# LED_PCB.net
KiCad netlist of a schematic drawn in EAGLE
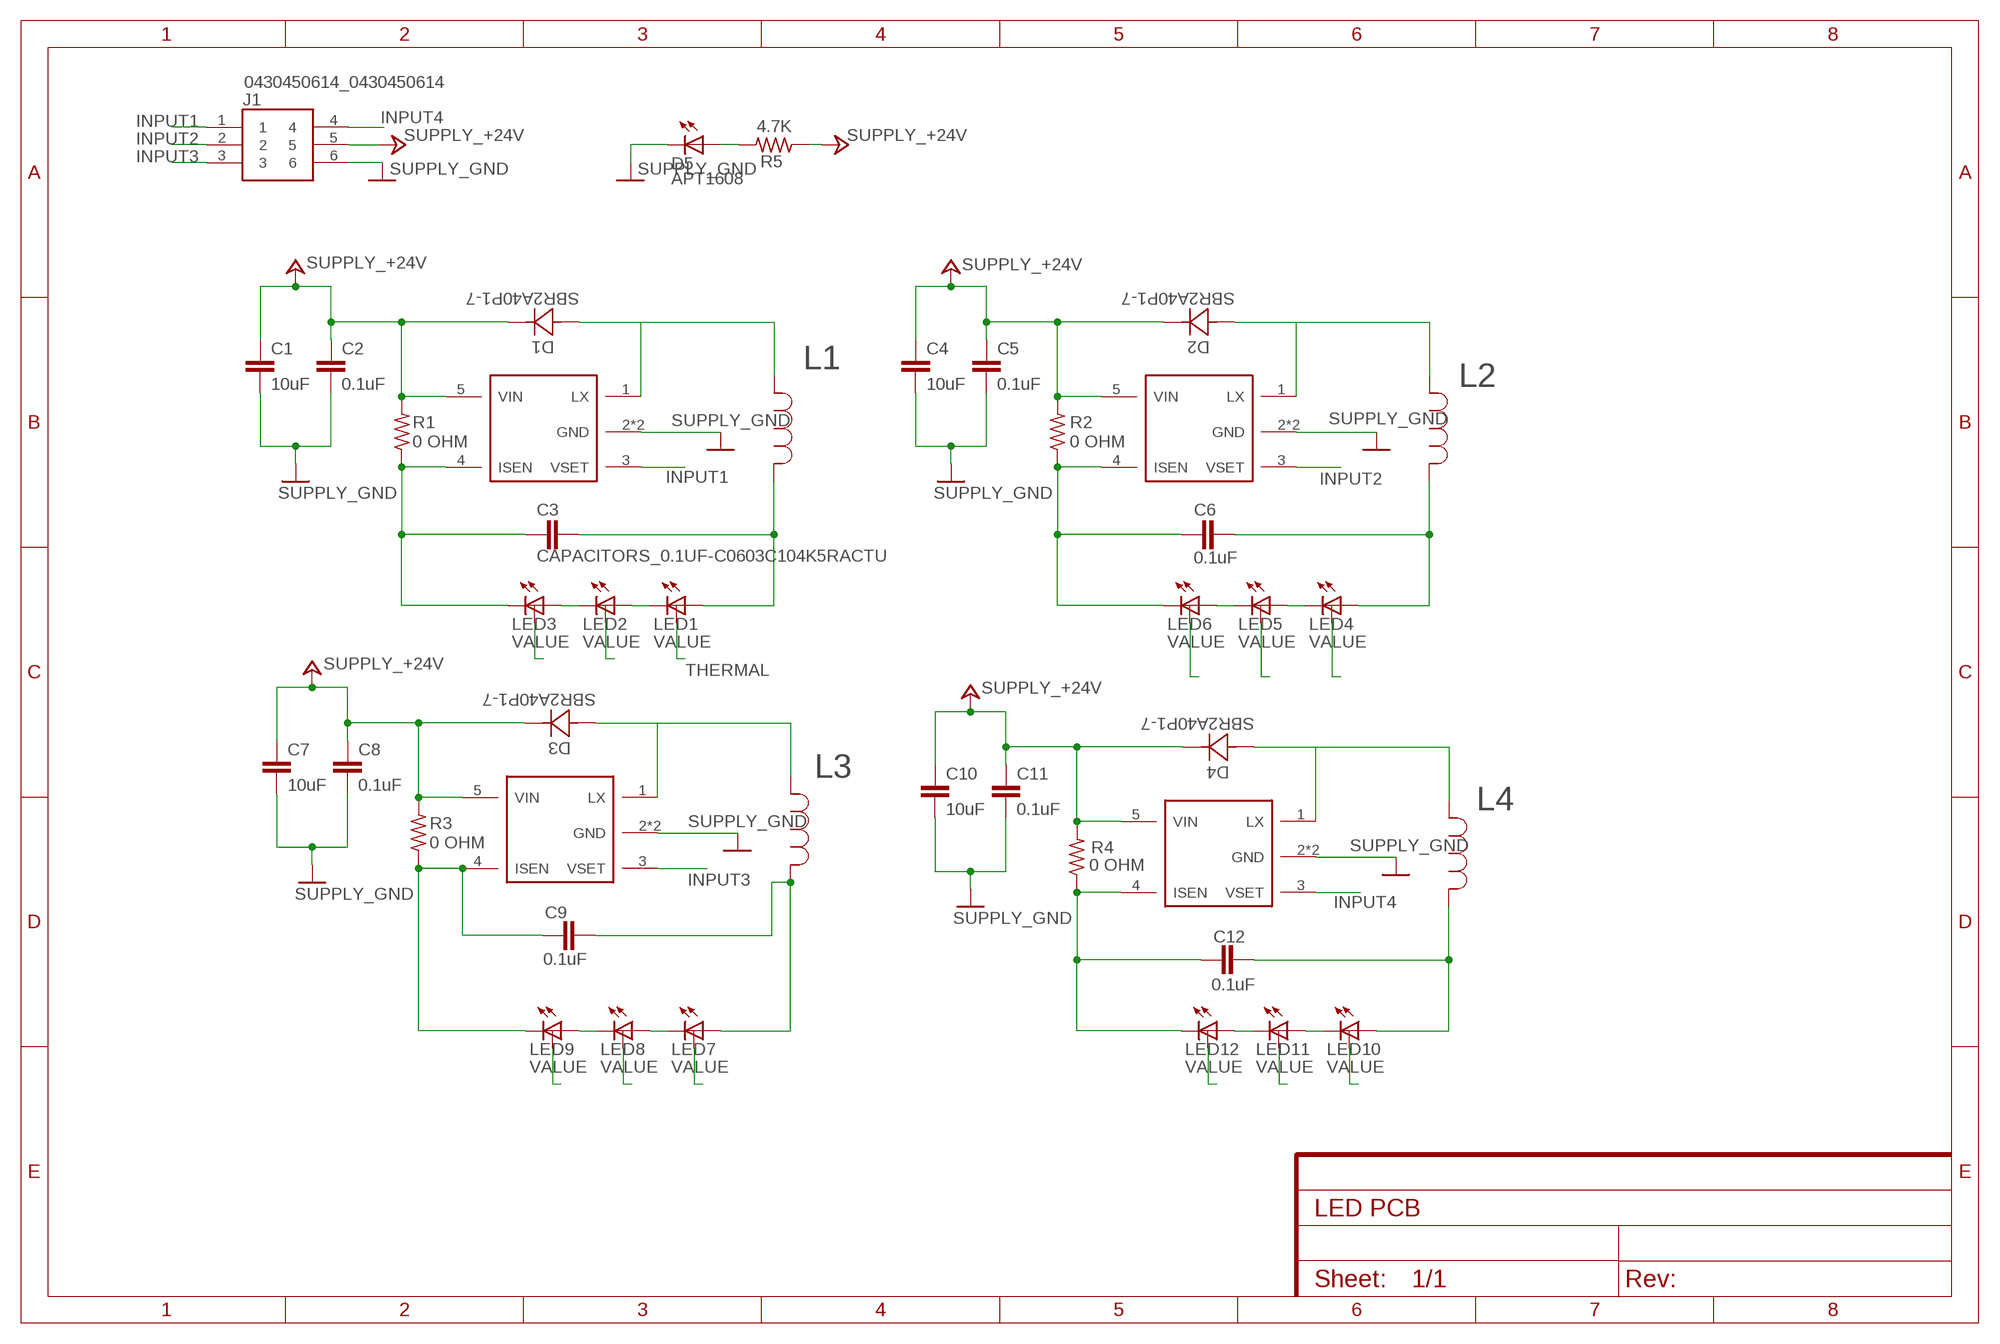
[diagram p0: schematic, sheet 1]

(export (version "E")
  (design (tool "Eeschema 10.0.6"))
  (components
    (comp (ref "C1")
      (value "10uF")
      (footprint "eagle-import:CAPACITORS_C0805")
      (fields (field (name "MANUFACTURER") "Taiyo Yuden") (field (name "MPN") "GMK212BBJ106KG-T"))
      (libsource (lib "eagle-import") (part "CAPACITORS_10UF-GMK212BBJ106KG-T"))
    )
    (comp (ref "C2")
      (value "0.1uF")
      (footprint "eagle-import:CAPACITORS_C0603")
      (fields (field (name "MANUFACTURER") "Kemet") (field (name "MPN") "C0603C104K5RACTU"))
      (libsource (lib "eagle-import") (part "CAPACITORS_0.1UF-C0603C104K5RACTU"))
    )
    (comp (ref "C3")
      (value "CAPACITORS_0.1UF-C0603C104K5RACTU")
      (footprint "eagle-import:CAPACITORS_C0603")
      (fields (field (name "MANUFACTURER") "Kemet") (field (name "MPN") "C0603C104K5RACTU"))
      (libsource (lib "eagle-import") (part "CAPACITORS_0.1UF-C0603C104K5RACTU"))
    )
    (comp (ref "C4")
      (value "10uF")
      (footprint "eagle-import:CAPACITORS_C0805")
      (fields (field (name "MANUFACTURER") "Taiyo Yuden") (field (name "MPN") "GMK212BBJ106KG-T"))
      (libsource (lib "eagle-import") (part "CAPACITORS_10UF-GMK212BBJ106KG-T"))
    )
    (comp (ref "C5")
      (value "0.1uF")
      (footprint "eagle-import:CAPACITORS_C0603")
      (fields (field (name "MANUFACTURER") "Kemet") (field (name "MPN") "C0603C104K5RACTU"))
      (libsource (lib "eagle-import") (part "CAPACITORS_0.1UF-C0603C104K5RACTU"))
    )
    (comp (ref "C6")
      (value "0.1uF")
      (footprint "eagle-import:CAPACITORS_C0603")
      (fields (field (name "MANUFACTURER") "Kemet") (field (name "MPN") "C0603C104K5RACTU"))
      (libsource (lib "eagle-import") (part "CAPACITORS_0.1UF-C0603C104K5RACTU"))
    )
    (comp (ref "C7")
      (value "10uF")
      (footprint "eagle-import:CAPACITORS_C0805")
      (fields (field (name "MANUFACTURER") "Taiyo Yuden") (field (name "MPN") "GMK212BBJ106KG-T"))
      (libsource (lib "eagle-import") (part "CAPACITORS_10UF-GMK212BBJ106KG-T"))
    )
    (comp (ref "C8")
      (value "0.1uF")
      (footprint "eagle-import:CAPACITORS_C0603")
      (fields (field (name "MANUFACTURER") "Kemet") (field (name "MPN") "C0603C104K5RACTU"))
      (libsource (lib "eagle-import") (part "CAPACITORS_0.1UF-C0603C104K5RACTU"))
    )
    (comp (ref "C9")
      (value "0.1uF")
      (footprint "eagle-import:CAPACITORS_C0603")
      (fields (field (name "MANUFACTURER") "Kemet") (field (name "MPN") "C0603C104K5RACTU"))
      (libsource (lib "eagle-import") (part "CAPACITORS_0.1UF-C0603C104K5RACTU"))
    )
    (comp (ref "C10")
      (value "10uF")
      (footprint "eagle-import:CAPACITORS_C0805")
      (fields (field (name "MANUFACTURER") "Taiyo Yuden") (field (name "MPN") "GMK212BBJ106KG-T"))
      (libsource (lib "eagle-import") (part "CAPACITORS_10UF-GMK212BBJ106KG-T"))
    )
    (comp (ref "C11")
      (value "0.1uF")
      (footprint "eagle-import:CAPACITORS_C0603")
      (fields (field (name "MANUFACTURER") "Kemet") (field (name "MPN") "C0603C104K5RACTU"))
      (libsource (lib "eagle-import") (part "CAPACITORS_0.1UF-C0603C104K5RACTU"))
    )
    (comp (ref "C12")
      (value "0.1uF")
      (footprint "eagle-import:CAPACITORS_C0603")
      (fields (field (name "MANUFACTURER") "Kemet") (field (name "MPN") "C0603C104K5RACTU"))
      (libsource (lib "eagle-import") (part "CAPACITORS_0.1UF-C0603C104K5RACTU"))
    )
    (comp (ref "D1")
      (value "SBR2A40P1-7")
      (footprint "eagle-import:DIODES_POWERDI123")
      (fields (field (name "MANUFACTURER") "Diodes Incorporated"))
      (libsource (lib "eagle-import") (part "DIODES_SBR2A40P1-7"))
    )
    (comp (ref "D2")
      (value "SBR2A40P1-7")
      (footprint "eagle-import:DIODES_POWERDI123")
      (fields (field (name "MANUFACTURER") "Diodes Incorporated"))
      (libsource (lib "eagle-import") (part "DIODES_SBR2A40P1-7"))
    )
    (comp (ref "D3")
      (value "SBR2A40P1-7")
      (footprint "eagle-import:DIODES_POWERDI123")
      (fields (field (name "MANUFACTURER") "Diodes Incorporated"))
      (libsource (lib "eagle-import") (part "DIODES_SBR2A40P1-7"))
    )
    (comp (ref "D4")
      (value "SBR2A40P1-7")
      (footprint "eagle-import:DIODES_POWERDI123")
      (fields (field (name "MANUFACTURER") "Diodes Incorporated"))
      (libsource (lib "eagle-import") (part "DIODES_SBR2A40P1-7"))
    )
    (comp (ref "D5")
      (value "APT1608")
      (footprint "eagle-import:DIODES_CHIPLED_0603")
      (fields (field (name "MANUFACTURER") "Kingbright") (field (name "MPN") "APT1608CGCK"))
      (libsource (lib "eagle-import") (part "DIODES_APT1608CGCK"))
    )
    (comp (ref "J1")
      (value "0430450614_0430450614")
      (footprint "eagle-import:0430450614_MOLEX_0430450614")
      (fields (field (name "MF") "Molex") (field (name "MP") "0430450614"))
      (libsource (lib "eagle-import") (part "0430450614_0430450614"))
    )
    (comp (ref "L1")
      (value "INDUCTORS_100UH_BOURNES")
      (footprint "eagle-import:INDUCTORS_IND_BOURNS_SDR1307")
      (libsource (lib "eagle-import") (part "INDUCTORS_100UH_BOURNES"))
    )
    (comp (ref "L2")
      (value "INDUCTORS_100UH_BOURNES")
      (footprint "eagle-import:INDUCTORS_IND_BOURNS_SDR1307")
      (libsource (lib "eagle-import") (part "INDUCTORS_100UH_BOURNES"))
    )
    (comp (ref "L3")
      (value "INDUCTORS_100UH_BOURNES")
      (footprint "eagle-import:INDUCTORS_IND_BOURNS_SDR1307")
      (libsource (lib "eagle-import") (part "INDUCTORS_100UH_BOURNES"))
    )
    (comp (ref "L4")
      (value "INDUCTORS_100UH_BOURNES")
      (footprint "eagle-import:INDUCTORS_IND_BOURNS_SDR1307")
      (libsource (lib "eagle-import") (part "INDUCTORS_100UH_BOURNES"))
    )
    (comp (ref "LED1")
      (value "PFCEDU_V4_TOMASZEWSKI_LED_W/THERM-CREE_XP-E2")
      (footprint "eagle-import:TOMASZEWSKI_CREE-XLAMP@1")
      (libsource (lib "eagle-import") (part "PFCEDU_V4_TOMASZEWSKI_LED_W/THERM-CREE_XP-E2"))
    )
    (comp (ref "LED2")
      (value "TOMASZEWSKI_LED_W/THERM-CREE_XP-E2")
      (footprint "eagle-import:TOMASZEWSKI_CREE-XLAMP@1")
      (fields (field (name "SPICEPREFIX") "J"))
      (libsource (lib "eagle-import") (part "PFCEDU_V4_TOMASZEWSKI_LED_W/THERM-CREE_XP-E2"))
    )
    (comp (ref "LED3")
      (value "PFCEDU_V4_TOMASZEWSKI_LED_W/THERM-CREE_XP-E2")
      (footprint "eagle-import:TOMASZEWSKI_CREE-XLAMP@1")
      (libsource (lib "eagle-import") (part "PFCEDU_V4_TOMASZEWSKI_LED_W/THERM-CREE_XP-E2"))
    )
    (comp (ref "LED4")
      (value "PFCEDU_V4_TOMASZEWSKI_LED_W/THERM-CREE_XP-E2")
      (footprint "eagle-import:TOMASZEWSKI_CREE-XLAMP@1")
      (libsource (lib "eagle-import") (part "PFCEDU_V4_TOMASZEWSKI_LED_W/THERM-CREE_XP-E2"))
    )
    (comp (ref "LED5")
      (value "PFCEDU_V4_TOMASZEWSKI_LED_W/THERM-CREE_XP-E2")
      (footprint "eagle-import:TOMASZEWSKI_CREE-XLAMP@1")
      (libsource (lib "eagle-import") (part "PFCEDU_V4_TOMASZEWSKI_LED_W/THERM-CREE_XP-E2"))
    )
    (comp (ref "LED6")
      (value "PFCEDU_V4_TOMASZEWSKI_LED_W/THERM-CREE_XP-E2")
      (footprint "eagle-import:TOMASZEWSKI_CREE-XLAMP@1")
      (libsource (lib "eagle-import") (part "PFCEDU_V4_TOMASZEWSKI_LED_W/THERM-CREE_XP-E2"))
    )
    (comp (ref "LED7")
      (value "PFCEDU_V4_TOMASZEWSKI_LED_W/THERM-CREE_XP-E2")
      (footprint "eagle-import:TOMASZEWSKI_CREE-XLAMP@1")
      (libsource (lib "eagle-import") (part "PFCEDU_V4_TOMASZEWSKI_LED_W/THERM-CREE_XP-E2"))
    )
    (comp (ref "LED8")
      (value "PFCEDU_V4_TOMASZEWSKI_LED_W/THERM-CREE_XP-E2")
      (footprint "eagle-import:TOMASZEWSKI_CREE-XLAMP@1")
      (libsource (lib "eagle-import") (part "PFCEDU_V4_TOMASZEWSKI_LED_W/THERM-CREE_XP-E2"))
    )
    (comp (ref "LED9")
      (value "PFCEDU_V4_TOMASZEWSKI_LED_W/THERM-CREE_XP-E2")
      (footprint "eagle-import:TOMASZEWSKI_CREE-XLAMP@1")
      (libsource (lib "eagle-import") (part "PFCEDU_V4_TOMASZEWSKI_LED_W/THERM-CREE_XP-E2"))
    )
    (comp (ref "LED10")
      (value "PFCEDU_V4_TOMASZEWSKI_LED_W/THERM-CREE_XP-E2")
      (footprint "eagle-import:TOMASZEWSKI_CREE-XLAMP@1")
      (libsource (lib "eagle-import") (part "PFCEDU_V4_TOMASZEWSKI_LED_W/THERM-CREE_XP-E2"))
    )
    (comp (ref "LED11")
      (value "PFCEDU_V4_TOMASZEWSKI_LED_W/THERM-CREE_XP-E2")
      (footprint "eagle-import:TOMASZEWSKI_CREE-XLAMP@1")
      (libsource (lib "eagle-import") (part "PFCEDU_V4_TOMASZEWSKI_LED_W/THERM-CREE_XP-E2"))
    )
    (comp (ref "LED12")
      (value "PFCEDU_V4_TOMASZEWSKI_LED_W/THERM-CREE_XP-E2")
      (footprint "eagle-import:TOMASZEWSKI_CREE-XLAMP@1")
      (libsource (lib "eagle-import") (part "PFCEDU_V4_TOMASZEWSKI_LED_W/THERM-CREE_XP-E2"))
    )
    (comp (ref "R1")
      (value "0 OHM")
      (footprint "eagle-import:RESISTORS_RC0603N")
      (fields (field (name "MANUFACTURER") "Yageo") (field (name "MPN") "RC0603JR-070RL"))
      (libsource (lib "eagle-import") (part "RESISTORS_0OHM-RC0603JR-070RL"))
    )
    (comp (ref "R2")
      (value "0 OHM")
      (footprint "eagle-import:RESISTORS_RC0603N")
      (fields (field (name "MANUFACTURER") "Yageo") (field (name "MPN") "RC0603JR-070RL"))
      (libsource (lib "eagle-import") (part "RESISTORS_0OHM-RC0603JR-070RL"))
    )
    (comp (ref "R3")
      (value "0 OHM")
      (footprint "eagle-import:RESISTORS_RC0603N")
      (fields (field (name "MANUFACTURER") "Yageo") (field (name "MPN") "RC0603JR-070RL"))
      (libsource (lib "eagle-import") (part "RESISTORS_0OHM-RC0603JR-070RL"))
    )
    (comp (ref "R4")
      (value "0 OHM")
      (footprint "eagle-import:RESISTORS_RC0603N")
      (fields (field (name "MANUFACTURER") "Yageo") (field (name "MPN") "RC0603JR-070RL"))
      (libsource (lib "eagle-import") (part "RESISTORS_0OHM-RC0603JR-070RL"))
    )
    (comp (ref "R5")
      (value "4.7K")
      (footprint "eagle-import:RESISTORS_R1206")
      (fields (field (name "MANUFACTURER") "Yageo") (field (name "MPN") "RC1206JR-074K7L"))
      (libsource (lib "eagle-import") (part "RESISTORS_4.7K-RC1206JR-074K7L"))
    )
    (comp (ref "U$1")
      (value "DRIVER-IC_AL8861")
      (footprint "eagle-import:DRIVER-IC_AL8861")
      (libsource (lib "eagle-import") (part "DRIVER-IC_AL8861"))
    )
    (comp (ref "U$3")
      (value "DRIVER-IC_AL8861")
      (footprint "eagle-import:DRIVER-IC_AL8861")
      (libsource (lib "eagle-import") (part "DRIVER-IC_AL8861"))
    )
    (comp (ref "U$5")
      (value "DRIVER-IC_AL8861")
      (footprint "eagle-import:DRIVER-IC_AL8861")
      (libsource (lib "eagle-import") (part "DRIVER-IC_AL8861"))
    )
    (comp (ref "U$7")
      (value "DRIVER-IC_AL8861")
      (footprint "eagle-import:DRIVER-IC_AL8861")
      (libsource (lib "eagle-import") (part "DRIVER-IC_AL8861"))
    )
  )
  (nets
    (net (code "1") (name "/INPUT1") (class "Default")
      (node (ref "J1") (pin "1") (pinfunction "1_1") (pintype "passive"))
      (node (ref "U$1") (pin "3") (pinfunction "VSET_3") (pintype "bidirectional"))
    )
    (net (code "2") (name "/INPUT2") (class "Default")
      (node (ref "J1") (pin "2") (pinfunction "2_2") (pintype "passive"))
      (node (ref "U$3") (pin "3") (pinfunction "VSET_3") (pintype "bidirectional"))
    )
    (net (code "3") (name "/INPUT3") (class "Default")
      (node (ref "J1") (pin "3") (pinfunction "3_3") (pintype "passive"))
      (node (ref "U$5") (pin "3") (pinfunction "VSET_3") (pintype "bidirectional"))
    )
    (net (code "4") (name "/INPUT4") (class "Default")
      (node (ref "J1") (pin "4") (pinfunction "4_4") (pintype "passive"))
      (node (ref "U$7") (pin "3") (pinfunction "VSET_3") (pintype "bidirectional"))
    )
    (net (code "5") (name "/THERMAL") (class "Default")
      (node (ref "LED1") (pin "THERM") (pinfunction "THERM_THERM") (pintype "bidirectional"))
    )
    (net (code "6") (name "Net-(C3-Pad2)") (class "Default")
      (node (ref "C3") (pin "2") (pinfunction "2_2") (pintype "passive"))
      (node (ref "L1") (pin "1") (pinfunction "1_1") (pintype "passive"))
      (node (ref "LED1") (pin "A") (pinfunction "A_A") (pintype "passive"))
      (node (ref "LED1") (pin "A@1") (pinfunction "A_A@1") (pintype "passive"))
    )
    (net (code "7") (name "Net-(C6-Pad2)") (class "Default")
      (node (ref "C6") (pin "2") (pinfunction "2_2") (pintype "passive"))
      (node (ref "L2") (pin "1") (pinfunction "1_1") (pintype "passive"))
      (node (ref "LED4") (pin "A") (pinfunction "A_A") (pintype "passive"))
      (node (ref "LED4") (pin "A@1") (pinfunction "A_A@1") (pintype "passive"))
    )
    (net (code "8") (name "Net-(C9-Pad2)") (class "Default")
      (node (ref "C9") (pin "2") (pinfunction "2_2") (pintype "passive"))
      (node (ref "L3") (pin "1") (pinfunction "1_1") (pintype "passive"))
      (node (ref "LED7") (pin "A") (pinfunction "A_A") (pintype "passive"))
      (node (ref "LED7") (pin "A@1") (pinfunction "A_A@1") (pintype "passive"))
    )
    (net (code "9") (name "Net-(C12-Pad2)") (class "Default")
      (node (ref "C12") (pin "2") (pinfunction "2_2") (pintype "passive"))
      (node (ref "L4") (pin "1") (pinfunction "1_1") (pintype "passive"))
      (node (ref "LED10") (pin "A") (pinfunction "A_A") (pintype "passive"))
      (node (ref "LED10") (pin "A@1") (pinfunction "A_A@1") (pintype "passive"))
    )
    (net (code "10") (name "Net-(D5-PadA)") (class "Default")
      (node (ref "D5") (pin "A") (pinfunction "A_A") (pintype "passive"))
      (node (ref "R5") (pin "2") (pinfunction "2_2") (pintype "passive"))
    )
    (net (code "11") (name "Net-(LED1-C-PadC@1)") (class "Default")
      (node (ref "LED1") (pin "C") (pinfunction "C_C") (pintype "passive"))
      (node (ref "LED1") (pin "C@1") (pinfunction "C_C@1") (pintype "passive"))
      (node (ref "LED2") (pin "A") (pinfunction "A_A") (pintype "passive"))
      (node (ref "LED2") (pin "A@1") (pinfunction "A_A@1") (pintype "passive"))
    )
    (net (code "12") (name "Net-(LED2-C-PadC@1)") (class "Default")
      (node (ref "LED2") (pin "C") (pinfunction "C_C") (pintype "passive"))
      (node (ref "LED2") (pin "C@1") (pinfunction "C_C@1") (pintype "passive"))
      (node (ref "LED3") (pin "A") (pinfunction "A_A") (pintype "passive"))
      (node (ref "LED3") (pin "A@1") (pinfunction "A_A@1") (pintype "passive"))
    )
    (net (code "13") (name "Net-(LED4-C-PadC@1)") (class "Default")
      (node (ref "LED4") (pin "C") (pinfunction "C_C") (pintype "passive"))
      (node (ref "LED4") (pin "C@1") (pinfunction "C_C@1") (pintype "passive"))
      (node (ref "LED5") (pin "A") (pinfunction "A_A") (pintype "passive"))
      (node (ref "LED5") (pin "A@1") (pinfunction "A_A@1") (pintype "passive"))
    )
    (net (code "14") (name "Net-(LED5-C-PadC@1)") (class "Default")
      (node (ref "LED5") (pin "C") (pinfunction "C_C") (pintype "passive"))
      (node (ref "LED5") (pin "C@1") (pinfunction "C_C@1") (pintype "passive"))
      (node (ref "LED6") (pin "A") (pinfunction "A_A") (pintype "passive"))
      (node (ref "LED6") (pin "A@1") (pinfunction "A_A@1") (pintype "passive"))
    )
    (net (code "15") (name "Net-(LED7-C-PadC@1)") (class "Default")
      (node (ref "LED7") (pin "C") (pinfunction "C_C") (pintype "passive"))
      (node (ref "LED7") (pin "C@1") (pinfunction "C_C@1") (pintype "passive"))
      (node (ref "LED8") (pin "A") (pinfunction "A_A") (pintype "passive"))
      (node (ref "LED8") (pin "A@1") (pinfunction "A_A@1") (pintype "passive"))
    )
    (net (code "16") (name "Net-(LED8-C-PadC@1)") (class "Default")
      (node (ref "LED8") (pin "C") (pinfunction "C_C") (pintype "passive"))
      (node (ref "LED8") (pin "C@1") (pinfunction "C_C@1") (pintype "passive"))
      (node (ref "LED9") (pin "A") (pinfunction "A_A") (pintype "passive"))
      (node (ref "LED9") (pin "A@1") (pinfunction "A_A@1") (pintype "passive"))
    )
    (net (code "17") (name "Net-(LED10-C-PadC@1)") (class "Default")
      (node (ref "LED10") (pin "C") (pinfunction "C_C") (pintype "passive"))
      (node (ref "LED10") (pin "C@1") (pinfunction "C_C@1") (pintype "passive"))
      (node (ref "LED11") (pin "A") (pinfunction "A_A") (pintype "passive"))
      (node (ref "LED11") (pin "A@1") (pinfunction "A_A@1") (pintype "passive"))
    )
    (net (code "18") (name "Net-(LED11-C-PadC@1)") (class "Default")
      (node (ref "LED11") (pin "C") (pinfunction "C_C") (pintype "passive"))
      (node (ref "LED11") (pin "C@1") (pinfunction "C_C@1") (pintype "passive"))
      (node (ref "LED12") (pin "A") (pinfunction "A_A") (pintype "passive"))
      (node (ref "LED12") (pin "A@1") (pinfunction "A_A@1") (pintype "passive"))
    )
    (net (code "19") (name "Net-(U$1-ISEN)") (class "Default")
      (node (ref "C3") (pin "1") (pinfunction "1_1") (pintype "passive"))
      (node (ref "LED3") (pin "C") (pinfunction "C_C") (pintype "passive"))
      (node (ref "LED3") (pin "C@1") (pinfunction "C_C@1") (pintype "passive"))
      (node (ref "R1") (pin "1") (pinfunction "1_1") (pintype "passive"))
      (node (ref "U$1") (pin "4") (pinfunction "ISEN_4") (pintype "bidirectional"))
    )
    (net (code "20") (name "Net-(U$1-LX)") (class "Default")
      (node (ref "D1") (pin "+") (pinfunction "+_+") (pintype "passive"))
      (node (ref "L1") (pin "2") (pinfunction "2_2") (pintype "passive"))
      (node (ref "U$1") (pin "1") (pinfunction "LX_1") (pintype "bidirectional"))
    )
    (net (code "21") (name "Net-(U$3-ISEN)") (class "Default")
      (node (ref "C6") (pin "1") (pinfunction "1_1") (pintype "passive"))
      (node (ref "LED6") (pin "C") (pinfunction "C_C") (pintype "passive"))
      (node (ref "LED6") (pin "C@1") (pinfunction "C_C@1") (pintype "passive"))
      (node (ref "R2") (pin "1") (pinfunction "1_1") (pintype "passive"))
      (node (ref "U$3") (pin "4") (pinfunction "ISEN_4") (pintype "bidirectional"))
    )
    (net (code "22") (name "Net-(U$3-LX)") (class "Default")
      (node (ref "D2") (pin "+") (pinfunction "+_+") (pintype "passive"))
      (node (ref "L2") (pin "2") (pinfunction "2_2") (pintype "passive"))
      (node (ref "U$3") (pin "1") (pinfunction "LX_1") (pintype "bidirectional"))
    )
    (net (code "23") (name "Net-(U$5-ISEN)") (class "Default")
      (node (ref "C9") (pin "1") (pinfunction "1_1") (pintype "passive"))
      (node (ref "LED9") (pin "C") (pinfunction "C_C") (pintype "passive"))
      (node (ref "LED9") (pin "C@1") (pinfunction "C_C@1") (pintype "passive"))
      (node (ref "R3") (pin "1") (pinfunction "1_1") (pintype "passive"))
      (node (ref "U$5") (pin "4") (pinfunction "ISEN_4") (pintype "bidirectional"))
    )
    (net (code "24") (name "Net-(U$5-LX)") (class "Default")
      (node (ref "D3") (pin "+") (pinfunction "+_+") (pintype "passive"))
      (node (ref "L3") (pin "2") (pinfunction "2_2") (pintype "passive"))
      (node (ref "U$5") (pin "1") (pinfunction "LX_1") (pintype "bidirectional"))
    )
    (net (code "25") (name "Net-(U$7-ISEN)") (class "Default")
      (node (ref "C12") (pin "1") (pinfunction "1_1") (pintype "passive"))
      (node (ref "LED12") (pin "C") (pinfunction "C_C") (pintype "passive"))
      (node (ref "LED12") (pin "C@1") (pinfunction "C_C@1") (pintype "passive"))
      (node (ref "R4") (pin "1") (pinfunction "1_1") (pintype "passive"))
      (node (ref "U$7") (pin "4") (pinfunction "ISEN_4") (pintype "bidirectional"))
    )
    (net (code "26") (name "Net-(U$7-LX)") (class "Default")
      (node (ref "D4") (pin "+") (pinfunction "+_+") (pintype "passive"))
      (node (ref "L4") (pin "2") (pinfunction "2_2") (pintype "passive"))
      (node (ref "U$7") (pin "1") (pinfunction "LX_1") (pintype "bidirectional"))
    )
    (net (code "27") (name "SUPPLY_+24V") (class "Default")
      (node (ref "C1") (pin "1") (pinfunction "1_1") (pintype "passive"))
      (node (ref "C10") (pin "1") (pinfunction "1_1") (pintype "passive"))
      (node (ref "C11") (pin "1") (pinfunction "1_1") (pintype "passive"))
      (node (ref "C2") (pin "1") (pinfunction "1_1") (pintype "passive"))
      (node (ref "C4") (pin "1") (pinfunction "1_1") (pintype "passive"))
      (node (ref "C5") (pin "1") (pinfunction "1_1") (pintype "passive"))
      (node (ref "C7") (pin "1") (pinfunction "1_1") (pintype "passive"))
      (node (ref "C8") (pin "1") (pinfunction "1_1") (pintype "passive"))
      (node (ref "D1") (pin "-") (pinfunction "-_-") (pintype "passive"))
      (node (ref "D2") (pin "-") (pinfunction "-_-") (pintype "passive"))
      (node (ref "D3") (pin "-") (pinfunction "-_-") (pintype "passive"))
      (node (ref "D4") (pin "-") (pinfunction "-_-") (pintype "passive"))
      (node (ref "J1") (pin "5") (pinfunction "5_5") (pintype "passive"))
      (node (ref "R1") (pin "2") (pinfunction "2_2") (pintype "passive"))
      (node (ref "R2") (pin "2") (pinfunction "2_2") (pintype "passive"))
      (node (ref "R3") (pin "2") (pinfunction "2_2") (pintype "passive"))
      (node (ref "R4") (pin "2") (pinfunction "2_2") (pintype "passive"))
      (node (ref "R5") (pin "1") (pinfunction "1_1") (pintype "passive"))
      (node (ref "U$1") (pin "5") (pinfunction "VIN_5") (pintype "bidirectional"))
      (node (ref "U$3") (pin "5") (pinfunction "VIN_5") (pintype "bidirectional"))
      (node (ref "U$5") (pin "5") (pinfunction "VIN_5") (pintype "bidirectional"))
      (node (ref "U$7") (pin "5") (pinfunction "VIN_5") (pintype "bidirectional"))
    )
    (net (code "28") (name "SUPPLY_GND") (class "Default")
      (node (ref "C1") (pin "2") (pinfunction "2_2") (pintype "passive"))
      (node (ref "C10") (pin "2") (pinfunction "2_2") (pintype "passive"))
      (node (ref "C11") (pin "2") (pinfunction "2_2") (pintype "passive"))
      (node (ref "C2") (pin "2") (pinfunction "2_2") (pintype "passive"))
      (node (ref "C4") (pin "2") (pinfunction "2_2") (pintype "passive"))
      (node (ref "C5") (pin "2") (pinfunction "2_2") (pintype "passive"))
      (node (ref "C7") (pin "2") (pinfunction "2_2") (pintype "passive"))
      (node (ref "C8") (pin "2") (pinfunction "2_2") (pintype "passive"))
      (node (ref "D5") (pin "C") (pinfunction "C_C") (pintype "passive"))
      (node (ref "J1") (pin "6") (pinfunction "6_6") (pintype "passive"))
      (node (ref "U$1") (pin "2") (pinfunction "GND_2") (pintype "bidirectional"))
      (node (ref "U$1") (pin "44") (pinfunction "GND_44") (pintype "bidirectional"))
      (node (ref "U$3") (pin "2") (pinfunction "GND_2") (pintype "bidirectional"))
      (node (ref "U$3") (pin "44") (pinfunction "GND_44") (pintype "bidirectional"))
      (node (ref "U$5") (pin "2") (pinfunction "GND_2") (pintype "bidirectional"))
      (node (ref "U$5") (pin "44") (pinfunction "GND_44") (pintype "bidirectional"))
      (node (ref "U$7") (pin "2") (pinfunction "GND_2") (pintype "bidirectional"))
      (node (ref "U$7") (pin "44") (pinfunction "GND_44") (pintype "bidirectional"))
    )
    (net (code "29") (name "unconnected-(LED2-PadTHERM)") (class "Default")
      (node (ref "LED2") (pin "THERM") (pinfunction "THERM_THERM") (pintype "bidirectional"))
    )
    (net (code "30") (name "unconnected-(LED3-PadTHERM)") (class "Default")
      (node (ref "LED3") (pin "THERM") (pinfunction "THERM_THERM") (pintype "bidirectional"))
    )
    (net (code "31") (name "unconnected-(LED4-PadTHERM)") (class "Default")
      (node (ref "LED4") (pin "THERM") (pinfunction "THERM_THERM") (pintype "bidirectional"))
    )
    (net (code "32") (name "unconnected-(LED5-PadTHERM)") (class "Default")
      (node (ref "LED5") (pin "THERM") (pinfunction "THERM_THERM") (pintype "bidirectional"))
    )
    (net (code "33") (name "unconnected-(LED6-PadTHERM)") (class "Default")
      (node (ref "LED6") (pin "THERM") (pinfunction "THERM_THERM") (pintype "bidirectional"))
    )
    (net (code "34") (name "unconnected-(LED7-PadTHERM)") (class "Default")
      (node (ref "LED7") (pin "THERM") (pinfunction "THERM_THERM") (pintype "bidirectional"))
    )
    (net (code "35") (name "unconnected-(LED8-PadTHERM)") (class "Default")
      (node (ref "LED8") (pin "THERM") (pinfunction "THERM_THERM") (pintype "bidirectional"))
    )
    (net (code "36") (name "unconnected-(LED9-PadTHERM)") (class "Default")
      (node (ref "LED9") (pin "THERM") (pinfunction "THERM_THERM") (pintype "bidirectional"))
    )
    (net (code "37") (name "unconnected-(LED10-PadTHERM)") (class "Default")
      (node (ref "LED10") (pin "THERM") (pinfunction "THERM_THERM") (pintype "bidirectional"))
    )
    (net (code "38") (name "unconnected-(LED11-PadTHERM)") (class "Default")
      (node (ref "LED11") (pin "THERM") (pinfunction "THERM_THERM") (pintype "bidirectional"))
    )
    (net (code "39") (name "unconnected-(LED12-PadTHERM)") (class "Default")
      (node (ref "LED12") (pin "THERM") (pinfunction "THERM_THERM") (pintype "bidirectional"))
    )
  )
)
